# FTDIChip.net
KiCad netlist of a schematic drawn in Altium Designer
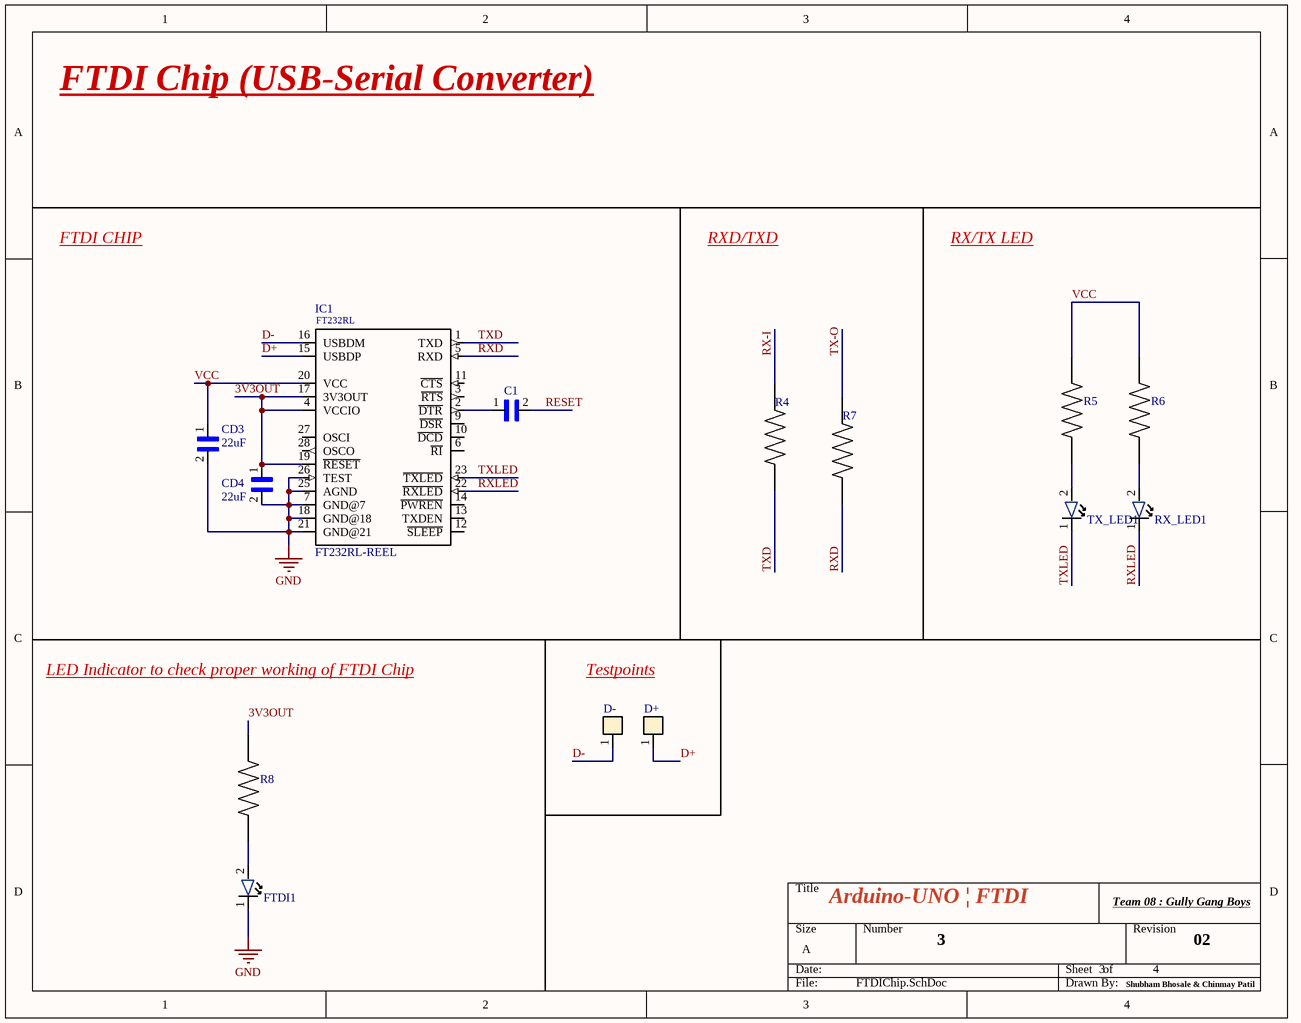
[diagram p0: FTDIChip.SchDoc]

(export (version "E")
  (design (tool "Eeschema 10.0.6"))
  (components
    (comp (ref "C1")
      (value "CL31A226MOCLNNC")
      (footprint "1206_Passive")
      (description "22µF ±20% 16V Ceramic Capacitor X5R 1206 (3216 Metric)")
      (fields (field (name "DIGIKEY PART") "1276-2728-1-ND"))
      (libsource (lib "brd2_rev2") (part "1206_22uF"))
    )
    (comp (ref "CD3")
      (value "22uF")
      (footprint "1206_Passive")
      (description "22µF ±20% 16V Ceramic Capacitor X5R 1206 (3216 Metric)")
      (fields (field (name "DIGIKEY PART") "1276-2728-1-ND"))
      (libsource (lib "brd2_rev2") (part "1206_22uF"))
    )
    (comp (ref "CD4")
      (value "22uF")
      (footprint "1206_Passive")
      (description "22µF ±20% 16V Ceramic Capacitor X5R 1206 (3216 Metric)")
      (fields (field (name "DIGIKEY PART") "1276-2728-1-ND"))
      (libsource (lib "brd2_rev2") (part "1206_22uF"))
    )
    (comp (ref "D+")
      (value "TESTPOINT")
      (footprint "TestPoint")
      (libsource (lib "brd2_rev2") (part "TESTPOINT"))
    )
    (comp (ref "D-")
      (value "TESTPOINT")
      (footprint "TestPoint")
      (libsource (lib "brd2_rev2") (part "TESTPOINT"))
    )
    (comp (ref "FTDI1")
      (value "LTST-C150CKT")
      (footprint "LED")
      (description "Red 638nm LED Indication - Discrete 1.8V 1206 (3216 Metric)")
      (fields (field (name "DIGIKEY PART") "160-1167-1-ND"))
      (libsource (lib "brd2_rev2") (part "1206_RED_LED"))
    )
    (comp (ref "IC1")
      (value "FT232RL-REEL")
      (footprint "FTDI")
      (description "USB Bridge, USB to UART USB 2.0 UART Interface 28-SSOP")
      (fields (field (name "DIGIKEY PART") "768-1007-1-ND"))
      (libsource (lib "brd2_rev2") (part "FTDI"))
    )
    (comp (ref "R4")
      (value "RNCP1206FTD1K00")
      (footprint "1206_Passive")
      (description "1 kOhms ±1% 0.5W, 1/2W Chip Resistor 1206 (3216 Metric) Anti-Sulfur, Moisture Resistant Thin Film")
      (fields (field (name "DIGIKEY PART") "RNCP1206FTD1K00CT-ND"))
      (libsource (lib "brd2_rev2") (part "1206_1K"))
    )
    (comp (ref "R5")
      (value "RNCP1206FTD1K00")
      (footprint "1206_Passive")
      (description "1 kOhms ±1% 0.5W, 1/2W Chip Resistor 1206 (3216 Metric) Anti-Sulfur, Moisture Resistant Thin Film")
      (fields (field (name "DIGIKEY PART") "RNCP1206FTD1K00CT-ND"))
      (libsource (lib "brd2_rev2") (part "1206_1K"))
    )
    (comp (ref "R6")
      (value "RNCP1206FTD1K00")
      (footprint "1206_Passive")
      (description "1 kOhms ±1% 0.5W, 1/2W Chip Resistor 1206 (3216 Metric) Anti-Sulfur, Moisture Resistant Thin Film")
      (fields (field (name "DIGIKEY PART") "RNCP1206FTD1K00CT-ND"))
      (libsource (lib "brd2_rev2") (part "1206_1K"))
    )
    (comp (ref "R7")
      (value "RNCP1206FTD1K00")
      (footprint "1206_Passive")
      (description "1 kOhms ±1% 0.5W, 1/2W Chip Resistor 1206 (3216 Metric) Anti-Sulfur, Moisture Resistant Thin Film")
      (fields (field (name "DIGIKEY PART") "RNCP1206FTD1K00CT-ND"))
      (libsource (lib "brd2_rev2") (part "1206_1K"))
    )
    (comp (ref "R8")
      (value "RNCP1206FTD1K00")
      (footprint "1206_Passive")
      (description "1 kOhms ±1% 0.5W, 1/2W Chip Resistor 1206 (3216 Metric) Anti-Sulfur, Moisture Resistant Thin Film")
      (fields (field (name "DIGIKEY PART") "RNCP1206FTD1K00CT-ND"))
      (libsource (lib "brd2_rev2") (part "1206_1K"))
    )
    (comp (ref "RX_LED1")
      (value "LTST-C150CKT")
      (footprint "LED")
      (description "Red 638nm LED Indication - Discrete 1.8V 1206 (3216 Metric)")
      (fields (field (name "DIGIKEY PART") "160-1167-1-ND"))
      (libsource (lib "brd2_rev2") (part "1206_RED_LED"))
    )
    (comp (ref "TX_LED1")
      (value "LTST-C150CKT")
      (footprint "LED")
      (description "Red 638nm LED Indication - Discrete 1.8V 1206 (3216 Metric)")
      (fields (field (name "DIGIKEY PART") "160-1167-1-ND"))
      (libsource (lib "brd2_rev2") (part "1206_RED_LED"))
    )
  )
  (nets
    (net (code "1") (name "/3V3OUT") (class "Default")
      (node (ref "CD4") (pin "1") (pinfunction "1_1") (pintype "passive"))
      (node (ref "IC1") (pin "17") (pinfunction "3V3OUT_17") (pintype "power_in"))
      (node (ref "IC1") (pin "19") (pinfunction "~{RESET}_19") (pintype "passive"))
      (node (ref "IC1") (pin "4") (pinfunction "VCCIO_4") (pintype "power_in"))
      (node (ref "R8") (pin "1") (pinfunction "1_1") (pintype "passive"))
    )
    (net (code "2") (name "/D+") (class "Default")
      (node (ref "D+") (pin "1") (pinfunction "1_1") (pintype "passive"))
      (node (ref "IC1") (pin "15") (pinfunction "USBDP_15") (pintype "bidirectional"))
    )
    (net (code "3") (name "/D-") (class "Default")
      (node (ref "D-") (pin "1") (pinfunction "1_1") (pintype "passive"))
      (node (ref "IC1") (pin "16") (pinfunction "USBDM_16") (pintype "bidirectional"))
    )
    (net (code "4") (name "/RESET") (class "Default")
      (node (ref "C1") (pin "2") (pinfunction "2_2") (pintype "passive"))
    )
    (net (code "5") (name "/RX-I") (class "Default")
      (node (ref "R4") (pin "2") (pinfunction "2_2") (pintype "passive"))
    )
    (net (code "6") (name "/RXD") (class "Default")
      (node (ref "IC1") (pin "5") (pinfunction "RXD_5") (pintype "input"))
      (node (ref "R7") (pin "1") (pinfunction "1_1") (pintype "passive"))
    )
    (net (code "7") (name "/RXLED") (class "Default")
      (node (ref "IC1") (pin "22") (pinfunction "~{RXLED}_22") (pintype "input"))
      (node (ref "RX_LED1") (pin "1") (pinfunction "1_1") (pintype "passive"))
    )
    (net (code "8") (name "/TX-O") (class "Default")
      (node (ref "R7") (pin "2") (pinfunction "2_2") (pintype "passive"))
    )
    (net (code "9") (name "/TXD") (class "Default")
      (node (ref "IC1") (pin "1") (pinfunction "TXD_1") (pintype "output"))
      (node (ref "R4") (pin "1") (pinfunction "1_1") (pintype "passive"))
    )
    (net (code "10") (name "/TXLED") (class "Default")
      (node (ref "IC1") (pin "23") (pinfunction "~{TXLED}_23") (pintype "input"))
      (node (ref "TX_LED1") (pin "1") (pinfunction "1_1") (pintype "passive"))
    )
    (net (code "11") (name "/VCC") (class "Default")
      (node (ref "CD3") (pin "1") (pinfunction "1_1") (pintype "passive"))
      (node (ref "IC1") (pin "20") (pinfunction "VCC_20") (pintype "power_in"))
      (node (ref "R5") (pin "1") (pinfunction "1_1") (pintype "passive"))
      (node (ref "R6") (pin "1") (pinfunction "1_1") (pintype "passive"))
    )
    (net (code "12") (name "GND") (class "Default")
      (node (ref "CD3") (pin "2") (pinfunction "2_2") (pintype "passive"))
      (node (ref "CD4") (pin "2") (pinfunction "2_2") (pintype "passive"))
      (node (ref "FTDI1") (pin "1") (pinfunction "1_1") (pintype "passive"))
      (node (ref "IC1") (pin "18") (pinfunction "GND@18_18") (pintype "power_in"))
      (node (ref "IC1") (pin "21") (pinfunction "GND@21_21") (pintype "power_in"))
      (node (ref "IC1") (pin "25") (pinfunction "AGND_25") (pintype "power_in"))
      (node (ref "IC1") (pin "26") (pinfunction "TEST_26") (pintype "input"))
      (node (ref "IC1") (pin "7") (pinfunction "GND@7_7") (pintype "power_in"))
    )
    (net (code "13") (name "Net-(FTDI1-Pad2)") (class "Default")
      (node (ref "FTDI1") (pin "2") (pinfunction "2_2") (pintype "passive"))
      (node (ref "R8") (pin "2") (pinfunction "2_2") (pintype "passive"))
    )
    (net (code "14") (name "Net-(IC1-~{DTR})") (class "Default")
      (node (ref "C1") (pin "1") (pinfunction "1_1") (pintype "passive"))
      (node (ref "IC1") (pin "2") (pinfunction "~{DTR}_2") (pintype "output"))
    )
    (net (code "15") (name "Net-(R5-Pad2)") (class "Default")
      (node (ref "R5") (pin "2") (pinfunction "2_2") (pintype "passive"))
      (node (ref "TX_LED1") (pin "2") (pinfunction "2_2") (pintype "passive"))
    )
    (net (code "16") (name "Net-(R6-Pad2)") (class "Default")
      (node (ref "R6") (pin "2") (pinfunction "2_2") (pintype "passive"))
      (node (ref "RX_LED1") (pin "2") (pinfunction "2_2") (pintype "passive"))
    )
    (net (code "17") (name "unconnected-(IC1-OSCI-Pad27)") (class "Default")
      (node (ref "IC1") (pin "27") (pinfunction "OSCI_27") (pintype "passive"))
    )
    (net (code "18") (name "unconnected-(IC1-OSCO-Pad28)") (class "Default")
      (node (ref "IC1") (pin "28") (pinfunction "OSCO_28") (pintype "output"))
    )
    (net (code "19") (name "unconnected-(IC1-TXDEN-Pad13)") (class "Default")
      (node (ref "IC1") (pin "13") (pinfunction "TXDEN_13") (pintype "passive"))
    )
    (net (code "20") (name "unconnected-(IC1-~{CTS}-Pad11)") (class "Default")
      (node (ref "IC1") (pin "11") (pinfunction "~{CTS}_11") (pintype "input"))
    )
    (net (code "21") (name "unconnected-(IC1-~{DCD}-Pad10)") (class "Default")
      (node (ref "IC1") (pin "10") (pinfunction "~{DCD}_10") (pintype "passive"))
    )
    (net (code "22") (name "unconnected-(IC1-~{DSR}-Pad9)") (class "Default")
      (node (ref "IC1") (pin "9") (pinfunction "~{DSR}_9") (pintype "passive"))
    )
    (net (code "23") (name "unconnected-(IC1-~{PWREN}-Pad14)") (class "Default")
      (node (ref "IC1") (pin "14") (pinfunction "~{PWREN}_14") (pintype "passive"))
    )
    (net (code "24") (name "unconnected-(IC1-~{RI}-Pad6)") (class "Default")
      (node (ref "IC1") (pin "6") (pinfunction "~{RI}_6") (pintype "passive"))
    )
    (net (code "25") (name "unconnected-(IC1-~{RTS}-Pad3)") (class "Default")
      (node (ref "IC1") (pin "3") (pinfunction "~{RTS}_3") (pintype "output"))
    )
    (net (code "26") (name "unconnected-(IC1-~{SLEEP}-Pad12)") (class "Default")
      (node (ref "IC1") (pin "12") (pinfunction "~{SLEEP}_12") (pintype "passive"))
    )
  )
)
